# main.net
KiCad netlist of a schematic drawn in EAGLE
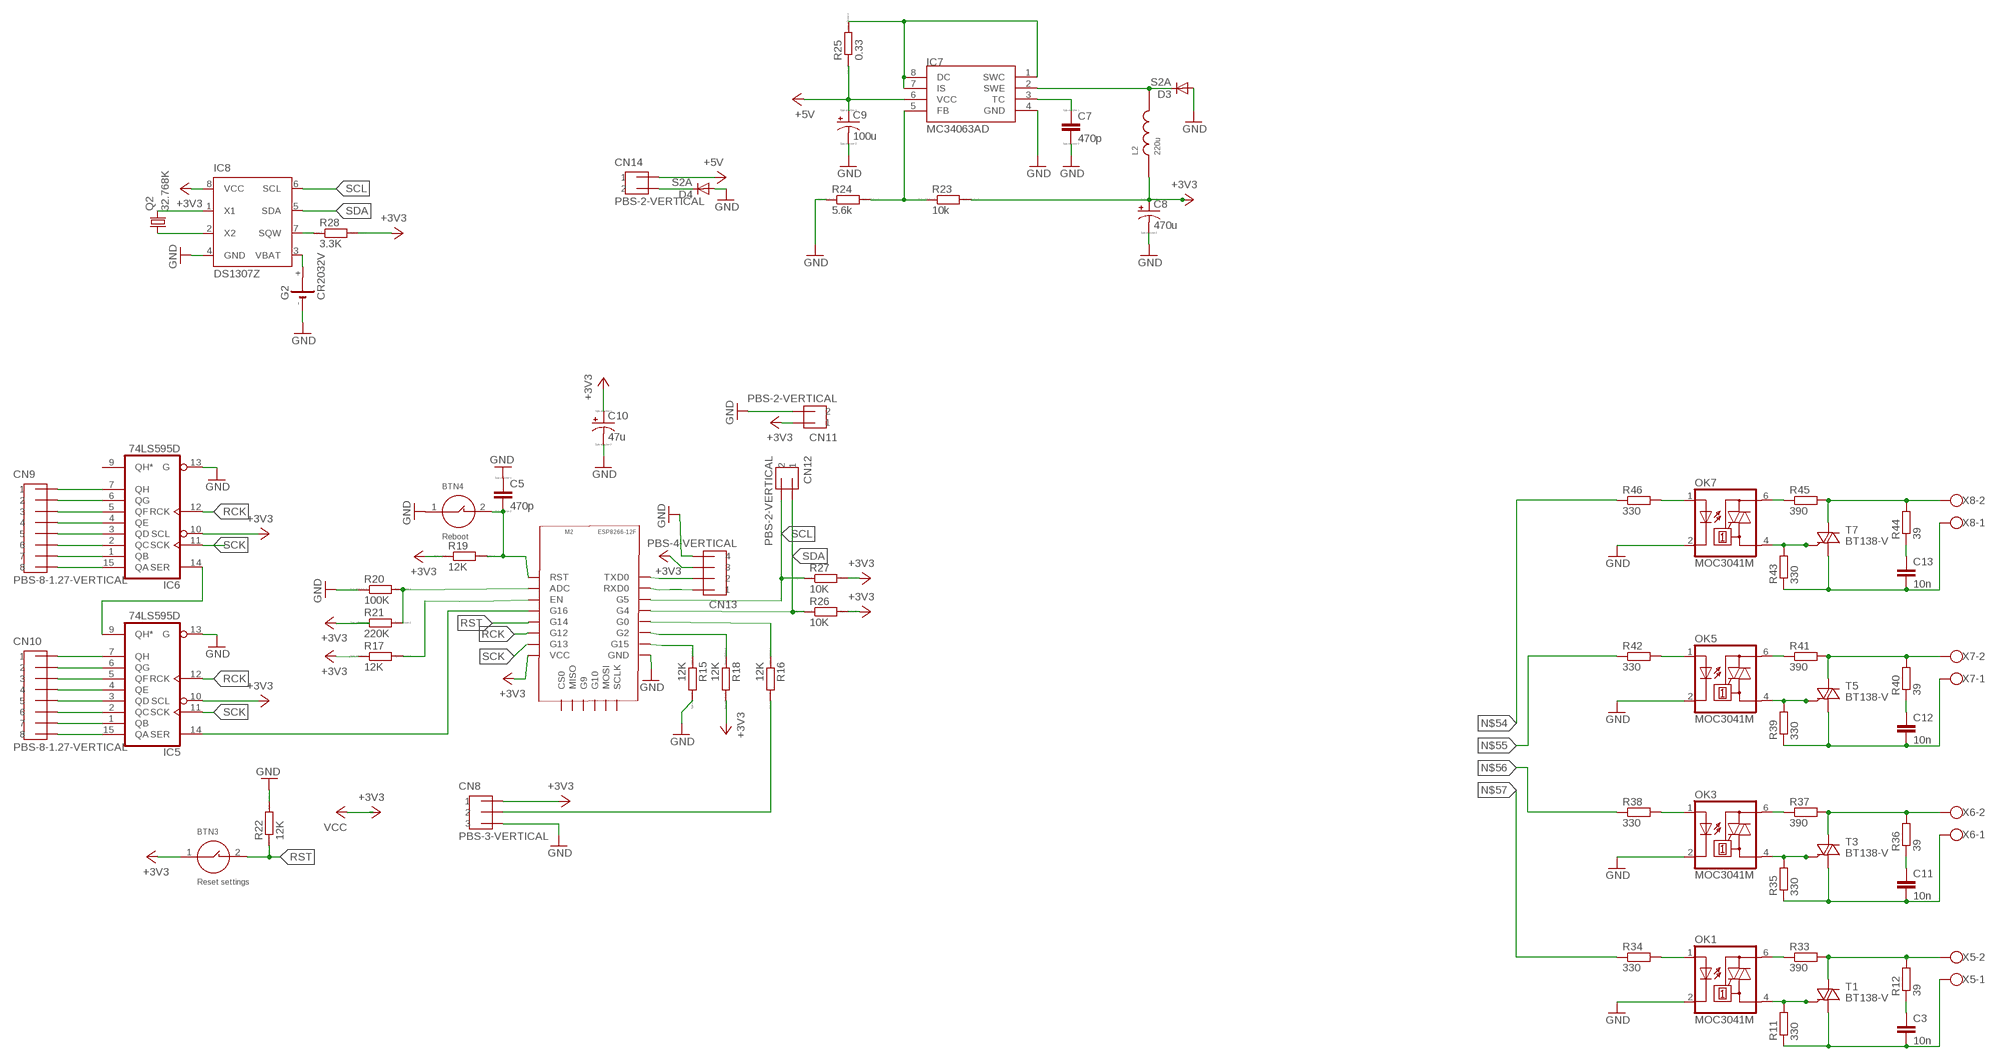
[diagram p0: schematic, sheet 1]

(export (version "E")
  (design (tool "Eeschema 10.0.6"))
  (components
    (comp (ref "BTN3")
      (value "Reset settings")
      (footprint "eagle-import:BTN-6X4-SMD")
      (libsource (lib "eagle-import") (part "BTN-6X4-SMD"))
    )
    (comp (ref "BTN4")
      (value "Reboot")
      (footprint "eagle-import:BTN-6X4-SMD")
      (libsource (lib "eagle-import") (part "BTN-6X4-SMD"))
    )
    (comp (ref "C3")
      (value "10n")
      (footprint "eagle-import:C10B5")
      (libsource (lib "eagle-import") (part "C10/5"))
    )
    (comp (ref "C5")
      (value "470p")
      (footprint "eagle-import:C0603")
      (libsource (lib "eagle-import") (part "CC0603"))
    )
    (comp (ref "C7")
      (value "470p")
      (footprint "eagle-import:C0603")
      (libsource (lib "eagle-import") (part "CC0603"))
    )
    (comp (ref "C8")
      (value "470u")
      (footprint "eagle-import:D_7343-31W")
      (libsource (lib "eagle-import") (part "CPOL-USD/7343-31W"))
    )
    (comp (ref "C9")
      (value "100u")
      (footprint "eagle-import:D_7343-31W")
      (libsource (lib "eagle-import") (part "CPOL-USD/7343-31W"))
    )
    (comp (ref "C10")
      (value "47u")
      (footprint "eagle-import:CT3216")
      (libsource (lib "eagle-import") (part "CPOL-USCT3216"))
    )
    (comp (ref "C11")
      (value "10n")
      (footprint "eagle-import:C10B5")
      (libsource (lib "eagle-import") (part "C10/5"))
    )
    (comp (ref "C12")
      (value "10n")
      (footprint "eagle-import:C10B5")
      (libsource (lib "eagle-import") (part "C10/5"))
    )
    (comp (ref "C13")
      (value "10n")
      (footprint "eagle-import:C10B5")
      (libsource (lib "eagle-import") (part "C10/5"))
    )
    (comp (ref "CN8")
      (value "PBS-3-VERTICAL")
      (footprint "eagle-import:PBS-3-VERTICAL")
      (libsource (lib "eagle-import") (part "PBS-3-VERTICAL"))
    )
    (comp (ref "CN9")
      (value "PBS-8-1.27-VERTICAL")
      (footprint "eagle-import:PBS-8-1.27-VERTICAL")
      (libsource (lib "eagle-import") (part "PBS-8-1.27-VERTICAL"))
    )
    (comp (ref "CN10")
      (value "PBS-8-1.27-VERTICAL")
      (footprint "eagle-import:PBS-8-1.27-VERTICAL")
      (libsource (lib "eagle-import") (part "PBS-8-1.27-VERTICAL"))
    )
    (comp (ref "CN11")
      (value "PBS-2-VERTICAL")
      (footprint "eagle-import:PBS-2-VERTICAL")
      (libsource (lib "eagle-import") (part "PBS-2-VERTICAL"))
    )
    (comp (ref "CN12")
      (value "PBS-2-VERTICAL")
      (footprint "eagle-import:PBS-2-VERTICAL")
      (libsource (lib "eagle-import") (part "PBS-2-VERTICAL"))
    )
    (comp (ref "CN13")
      (value "PBS-4-VERTICAL")
      (footprint "eagle-import:PBS-4-VERTICAL")
      (libsource (lib "eagle-import") (part "PBS-4-VERTICAL"))
    )
    (comp (ref "CN14")
      (value "PBS-2-VERTICAL")
      (footprint "eagle-import:PBS-2-VERTICAL")
      (libsource (lib "eagle-import") (part "PBS-2-VERTICAL"))
    )
    (comp (ref "D3")
      (value "S2A")
      (footprint "eagle-import:DO214AA")
      (fields (field (name "MF") "Fairchild"))
      (libsource (lib "eagle-import") (part "S2A"))
    )
    (comp (ref "D4")
      (value "S2A")
      (footprint "eagle-import:DO214AA")
      (fields (field (name "MF") "Fairchild"))
      (libsource (lib "eagle-import") (part "S2A"))
    )
    (comp (ref "G2")
      (value "CR2032V")
      (footprint "eagle-import:CR2032V")
      (libsource (lib "eagle-import") (part "CR2032V"))
    )
    (comp (ref "IC5")
      (value "74LS595D")
      (footprint "eagle-import:SO16")
      (libsource (lib "eagle-import") (part "74595DLS"))
    )
    (comp (ref "IC6")
      (value "74LS595D")
      (footprint "eagle-import:SO16")
      (libsource (lib "eagle-import") (part "74595DLS"))
    )
    (comp (ref "IC7")
      (value "MC34063AD")
      (footprint "eagle-import:SOIC8")
      (libsource (lib "eagle-import") (part "MC34063AD"))
    )
    (comp (ref "IC8")
      (value "DS1307Z")
      (footprint "eagle-import:SOIC8")
      (libsource (lib "eagle-import") (part "DS1307Z"))
    )
    (comp (ref "L2")
      (value "220u")
      (footprint "eagle-import:INDUCTOR-5-10")
      (libsource (lib "eagle-import") (part "INDUCTOR-5-10"))
    )
    (comp (ref "M2")
      (value "ESP8266-12F")
      (footprint "eagle-import:ESP8266-12F")
      (libsource (lib "eagle-import") (part "ESP8266-12F"))
    )
    (comp (ref "OK1")
      (value "MOC3041M")
      (footprint "eagle-import:DIL06")
      (fields (field (name "MF") "FAIRCHILD SEMICONDUCTOR"))
      (libsource (lib "eagle-import") (part "MOC3041M"))
    )
    (comp (ref "OK3")
      (value "MOC3041M")
      (footprint "eagle-import:DIL06")
      (fields (field (name "MF") "FAIRCHILD SEMICONDUCTOR"))
      (libsource (lib "eagle-import") (part "MOC3041M"))
    )
    (comp (ref "OK5")
      (value "MOC3041M")
      (footprint "eagle-import:DIL06")
      (fields (field (name "MF") "FAIRCHILD SEMICONDUCTOR"))
      (libsource (lib "eagle-import") (part "MOC3041M"))
    )
    (comp (ref "OK7")
      (value "MOC3041M")
      (footprint "eagle-import:DIL06")
      (fields (field (name "MF") "FAIRCHILD SEMICONDUCTOR"))
      (libsource (lib "eagle-import") (part "MOC3041M"))
    )
    (comp (ref "Q2")
      (value "32.768K")
      (footprint "eagle-import:TC38H")
      (libsource (lib "eagle-import") (part "CRYSTALTC38H"))
    )
    (comp (ref "R11")
      (value "330")
      (footprint "eagle-import:0411_12")
      (libsource (lib "eagle-import") (part "R-EU_0411/12"))
    )
    (comp (ref "R12")
      (value "39")
      (footprint "eagle-import:0411_12")
      (libsource (lib "eagle-import") (part "R-EU_0411/12"))
    )
    (comp (ref "R15")
      (value "12K")
      (footprint "eagle-import:R0603")
      (libsource (lib "eagle-import") (part "RR0603"))
    )
    (comp (ref "R16")
      (value "12K")
      (footprint "eagle-import:R0603")
      (libsource (lib "eagle-import") (part "RR0603"))
    )
    (comp (ref "R17")
      (value "12K")
      (footprint "eagle-import:R0603")
      (libsource (lib "eagle-import") (part "RR0603"))
    )
    (comp (ref "R18")
      (value "12K")
      (footprint "eagle-import:R0603")
      (libsource (lib "eagle-import") (part "RR0603"))
    )
    (comp (ref "R19")
      (value "12K")
      (footprint "eagle-import:R0603")
      (libsource (lib "eagle-import") (part "RR0603"))
    )
    (comp (ref "R20")
      (value "100K")
      (footprint "eagle-import:R0603")
      (libsource (lib "eagle-import") (part "RR0603"))
    )
    (comp (ref "R21")
      (value "220K")
      (footprint "eagle-import:R0603")
      (libsource (lib "eagle-import") (part "RR0603"))
    )
    (comp (ref "R22")
      (value "12K")
      (footprint "eagle-import:R0603")
      (libsource (lib "eagle-import") (part "RR0603"))
    )
    (comp (ref "R23")
      (value "10k")
      (footprint "eagle-import:R0603")
      (libsource (lib "eagle-import") (part "RR0603"))
    )
    (comp (ref "R24")
      (value "5.6k")
      (footprint "eagle-import:R0603")
      (libsource (lib "eagle-import") (part "RR0603"))
    )
    (comp (ref "R25")
      (value "0.33")
      (footprint "eagle-import:R0603")
      (libsource (lib "eagle-import") (part "RR0603"))
    )
    (comp (ref "R26")
      (value "10K")
      (footprint "eagle-import:R0603")
      (libsource (lib "eagle-import") (part "RR0603"))
    )
    (comp (ref "R27")
      (value "10K")
      (footprint "eagle-import:R0603")
      (libsource (lib "eagle-import") (part "RR0603"))
    )
    (comp (ref "R28")
      (value "3.3K")
      (footprint "eagle-import:R0603")
      (libsource (lib "eagle-import") (part "RR0603"))
    )
    (comp (ref "R33")
      (value "390")
      (footprint "eagle-import:0411_12")
      (libsource (lib "eagle-import") (part "R-EU_0411/12"))
    )
    (comp (ref "R34")
      (value "330")
      (footprint "eagle-import:R0603")
      (libsource (lib "eagle-import") (part "R-EU_R0603"))
    )
    (comp (ref "R35")
      (value "330")
      (footprint "eagle-import:0411_12")
      (libsource (lib "eagle-import") (part "R-EU_0411/12"))
    )
    (comp (ref "R36")
      (value "39")
      (footprint "eagle-import:0411_12")
      (libsource (lib "eagle-import") (part "R-EU_0411/12"))
    )
    (comp (ref "R37")
      (value "390")
      (footprint "eagle-import:0411_12")
      (libsource (lib "eagle-import") (part "R-EU_0411/12"))
    )
    (comp (ref "R38")
      (value "330")
      (footprint "eagle-import:R0603")
      (libsource (lib "eagle-import") (part "R-EU_R0603"))
    )
    (comp (ref "R39")
      (value "330")
      (footprint "eagle-import:0411_12")
      (libsource (lib "eagle-import") (part "R-EU_0411/12"))
    )
    (comp (ref "R40")
      (value "39")
      (footprint "eagle-import:0411_12")
      (libsource (lib "eagle-import") (part "R-EU_0411/12"))
    )
    (comp (ref "R41")
      (value "390")
      (footprint "eagle-import:0411_12")
      (libsource (lib "eagle-import") (part "R-EU_0411/12"))
    )
    (comp (ref "R42")
      (value "330")
      (footprint "eagle-import:R0603")
      (libsource (lib "eagle-import") (part "R-EU_R0603"))
    )
    (comp (ref "R43")
      (value "330")
      (footprint "eagle-import:0411_12")
      (libsource (lib "eagle-import") (part "R-EU_0411/12"))
    )
    (comp (ref "R44")
      (value "39")
      (footprint "eagle-import:0411_12")
      (libsource (lib "eagle-import") (part "R-EU_0411/12"))
    )
    (comp (ref "R45")
      (value "390")
      (footprint "eagle-import:0411_12")
      (libsource (lib "eagle-import") (part "R-EU_0411/12"))
    )
    (comp (ref "R46")
      (value "330")
      (footprint "eagle-import:R0603")
      (libsource (lib "eagle-import") (part "R-EU_R0603"))
    )
    (comp (ref "T1")
      (value "BT138-V")
      (footprint "eagle-import:TO220BV")
      (libsource (lib "eagle-import") (part "BT138-V"))
    )
    (comp (ref "T3")
      (value "BT138-V")
      (footprint "eagle-import:TO220BV")
      (libsource (lib "eagle-import") (part "BT138-V"))
    )
    (comp (ref "T5")
      (value "BT138-V")
      (footprint "eagle-import:TO220BV")
      (libsource (lib "eagle-import") (part "BT138-V"))
    )
    (comp (ref "T7")
      (value "BT138-V")
      (footprint "eagle-import:TO220BV")
      (libsource (lib "eagle-import") (part "BT138-V"))
    )
    (comp (ref "X5")
      (value "W237-102")
      (footprint "eagle-import:W237-102")
      (fields (field (name "MPN") "237-102"))
      (libsource (lib "eagle-import") (part "W237-102"))
    )
    (comp (ref "X6")
      (value "W237-102")
      (footprint "eagle-import:W237-102")
      (fields (field (name "MPN") "237-102"))
      (libsource (lib "eagle-import") (part "W237-102"))
    )
    (comp (ref "X7")
      (value "W237-102")
      (footprint "eagle-import:W237-102")
      (fields (field (name "MPN") "237-102"))
      (libsource (lib "eagle-import") (part "W237-102"))
    )
    (comp (ref "X8")
      (value "W237-102")
      (footprint "eagle-import:W237-102")
      (fields (field (name "MPN") "237-102"))
      (libsource (lib "eagle-import") (part "W237-102"))
    )
  )
  (nets
    (net (code "1") (name "+3V3") (class "Default")
      (node (ref "BTN3") (pin "1") (pinfunction "1_1") (pintype "bidirectional"))
      (node (ref "C10") (pin "-") (pinfunction "+_-") (pintype "passive"))
      (node (ref "C8") (pin "+") (pinfunction "+_+") (pintype "passive"))
      (node (ref "CN11") (pin "P$1") (pinfunction "1_P$1") (pintype "bidirectional"))
      (node (ref "CN13") (pin "P$3") (pinfunction "3_P$3") (pintype "bidirectional"))
      (node (ref "CN8") (pin "P$1") (pinfunction "1_P$1") (pintype "bidirectional"))
      (node (ref "IC5") (pin "10") (pinfunction "SCL_10") (pintype "input"))
      (node (ref "IC6") (pin "10") (pinfunction "SCL_10") (pintype "input"))
      (node (ref "IC8") (pin "8") (pinfunction "VCC_8") (pintype "power_in"))
      (node (ref "L2") (pin "P$1") (pinfunction "1_P$1") (pintype "bidirectional"))
      (node (ref "M2") (pin "VCC") (pinfunction "VCC_VCC") (pintype "power_in"))
      (node (ref "R17") (pin "1") (pinfunction "1_1") (pintype "passive"))
      (node (ref "R18") (pin "2") (pinfunction "2_2") (pintype "passive"))
      (node (ref "R19") (pin "1") (pinfunction "1_1") (pintype "passive"))
      (node (ref "R21") (pin "1") (pinfunction "1_1") (pintype "passive"))
      (node (ref "R23") (pin "2") (pinfunction "2_2") (pintype "passive"))
      (node (ref "R26") (pin "2") (pinfunction "2_2") (pintype "passive"))
      (node (ref "R27") (pin "2") (pinfunction "2_2") (pintype "passive"))
      (node (ref "R28") (pin "2") (pinfunction "2_2") (pintype "passive"))
    )
    (net (code "2") (name "+5V") (class "Default")
      (node (ref "C9") (pin "+") (pinfunction "+_+") (pintype "passive"))
      (node (ref "CN14") (pin "P$1") (pinfunction "1_P$1") (pintype "bidirectional"))
      (node (ref "IC7") (pin "6") (pinfunction "VCC_6") (pintype "passive"))
      (node (ref "R25") (pin "1") (pinfunction "1_1") (pintype "passive"))
    )
    (net (code "3") (name "/N$60") (class "Default")
      (node (ref "BTN4") (pin "2") (pinfunction "2_2") (pintype "bidirectional"))
      (node (ref "C5") (pin "2") (pinfunction "2_2") (pintype "passive"))
      (node (ref "M2") (pin "RST") (pinfunction "RST_RST") (pintype "bidirectional"))
      (node (ref "R19") (pin "2") (pinfunction "2_2") (pintype "passive"))
    )
    (net (code "4") (name "GND") (class "Default")
      (node (ref "BTN4") (pin "1") (pinfunction "1_1") (pintype "bidirectional"))
      (node (ref "C10") (pin "+") (pinfunction "-_+") (pintype "passive"))
      (node (ref "C5") (pin "1") (pinfunction "1_1") (pintype "passive"))
      (node (ref "C7") (pin "2") (pinfunction "2_2") (pintype "passive"))
      (node (ref "C8") (pin "-") (pinfunction "-_-") (pintype "passive"))
      (node (ref "C9") (pin "-") (pinfunction "-_-") (pintype "passive"))
      (node (ref "CN11") (pin "P$2") (pinfunction "2_P$2") (pintype "bidirectional"))
      (node (ref "CN13") (pin "P$4") (pinfunction "4_P$4") (pintype "bidirectional"))
      (node (ref "CN8") (pin "P$3") (pinfunction "3_P$3") (pintype "bidirectional"))
      (node (ref "D3") (pin "A") (pinfunction "A_A") (pintype "passive"))
      (node (ref "D4") (pin "A") (pinfunction "A_A") (pintype "passive"))
      (node (ref "G2") (pin "-") (pinfunction "-_-") (pintype "passive"))
      (node (ref "IC5") (pin "13") (pinfunction "G_13") (pintype "input"))
      (node (ref "IC6") (pin "13") (pinfunction "G_13") (pintype "input"))
      (node (ref "IC7") (pin "4") (pinfunction "GND_4") (pintype "passive"))
      (node (ref "IC8") (pin "4") (pinfunction "GND_4") (pintype "power_in"))
      (node (ref "M2") (pin "GND") (pinfunction "GND_GND") (pintype "power_in"))
      (node (ref "OK1") (pin "2") (pinfunction "C_2") (pintype "passive"))
      (node (ref "OK3") (pin "2") (pinfunction "C_2") (pintype "passive"))
      (node (ref "OK5") (pin "2") (pinfunction "C_2") (pintype "passive"))
      (node (ref "OK7") (pin "2") (pinfunction "C_2") (pintype "passive"))
      (node (ref "R15") (pin "2") (pinfunction "2_2") (pintype "passive"))
      (node (ref "R20") (pin "1") (pinfunction "1_1") (pintype "passive"))
      (node (ref "R22") (pin "2") (pinfunction "2_2") (pintype "passive"))
      (node (ref "R24") (pin "1") (pinfunction "1_1") (pintype "passive"))
    )
    (net (code "5") (name "N$54") (class "Default")
      (node (ref "CN10") (pin "P$5") (pinfunction "5_P$5") (pintype "bidirectional"))
      (node (ref "IC5") (pin "3") (pinfunction "QD_3") (pintype "tri_state"))
      (node (ref "R46") (pin "1") (pinfunction "1_1") (pintype "passive"))
    )
    (net (code "6") (name "N$55") (class "Default")
      (node (ref "CN10") (pin "P$6") (pinfunction "6_P$6") (pintype "bidirectional"))
      (node (ref "IC5") (pin "2") (pinfunction "QC_2") (pintype "tri_state"))
      (node (ref "R42") (pin "1") (pinfunction "1_1") (pintype "passive"))
    )
    (net (code "7") (name "N$56") (class "Default")
      (node (ref "CN10") (pin "P$7") (pinfunction "7_P$7") (pintype "bidirectional"))
      (node (ref "IC5") (pin "1") (pinfunction "QB_1") (pintype "tri_state"))
      (node (ref "R38") (pin "1") (pinfunction "1_1") (pintype "passive"))
    )
    (net (code "8") (name "N$57") (class "Default")
      (node (ref "CN10") (pin "P$8") (pinfunction "8_P$8") (pintype "bidirectional"))
      (node (ref "IC5") (pin "15") (pinfunction "QA_15") (pintype "tri_state"))
      (node (ref "R34") (pin "1") (pinfunction "1_1") (pintype "passive"))
    )
    (net (code "9") (name "Net-(C3-Pad1)") (class "Default")
      (node (ref "C3") (pin "1") (pinfunction "1_1") (pintype "passive"))
      (node (ref "R12") (pin "1") (pinfunction "1_1") (pintype "passive"))
    )
    (net (code "10") (name "Net-(C11-Pad1)") (class "Default")
      (node (ref "C11") (pin "1") (pinfunction "1_1") (pintype "passive"))
      (node (ref "R36") (pin "1") (pinfunction "1_1") (pintype "passive"))
    )
    (net (code "11") (name "Net-(C12-Pad1)") (class "Default")
      (node (ref "C12") (pin "1") (pinfunction "1_1") (pintype "passive"))
      (node (ref "R40") (pin "1") (pinfunction "1_1") (pintype "passive"))
    )
    (net (code "12") (name "Net-(C13-Pad1)") (class "Default")
      (node (ref "C13") (pin "1") (pinfunction "1_1") (pintype "passive"))
      (node (ref "R44") (pin "1") (pinfunction "1_1") (pintype "passive"))
    )
    (net (code "13") (name "Net-(CN8-2)") (class "Default")
      (node (ref "CN8") (pin "P$2") (pinfunction "2_P$2") (pintype "bidirectional"))
      (node (ref "R16") (pin "2") (pinfunction "2_2") (pintype "passive"))
    )
    (net (code "14") (name "Net-(CN9-1)") (class "Default")
      (node (ref "CN9") (pin "P$1") (pinfunction "1_P$1") (pintype "bidirectional"))
      (node (ref "IC6") (pin "7") (pinfunction "QH_7") (pintype "tri_state"))
    )
    (net (code "15") (name "Net-(CN9-2)") (class "Default")
      (node (ref "CN9") (pin "P$2") (pinfunction "2_P$2") (pintype "bidirectional"))
      (node (ref "IC6") (pin "6") (pinfunction "QG_6") (pintype "tri_state"))
    )
    (net (code "16") (name "Net-(CN9-3)") (class "Default")
      (node (ref "CN9") (pin "P$3") (pinfunction "3_P$3") (pintype "bidirectional"))
      (node (ref "IC6") (pin "5") (pinfunction "QF_5") (pintype "tri_state"))
    )
    (net (code "17") (name "Net-(CN9-4)") (class "Default")
      (node (ref "CN9") (pin "P$4") (pinfunction "4_P$4") (pintype "bidirectional"))
      (node (ref "IC6") (pin "4") (pinfunction "QE_4") (pintype "tri_state"))
    )
    (net (code "18") (name "Net-(CN9-5)") (class "Default")
      (node (ref "CN9") (pin "P$5") (pinfunction "5_P$5") (pintype "bidirectional"))
      (node (ref "IC6") (pin "3") (pinfunction "QD_3") (pintype "tri_state"))
    )
    (net (code "19") (name "Net-(CN9-6)") (class "Default")
      (node (ref "CN9") (pin "P$6") (pinfunction "6_P$6") (pintype "bidirectional"))
      (node (ref "IC6") (pin "2") (pinfunction "QC_2") (pintype "tri_state"))
    )
    (net (code "20") (name "Net-(CN9-7)") (class "Default")
      (node (ref "CN9") (pin "P$7") (pinfunction "7_P$7") (pintype "bidirectional"))
      (node (ref "IC6") (pin "1") (pinfunction "QB_1") (pintype "tri_state"))
    )
    (net (code "21") (name "Net-(CN9-8)") (class "Default")
      (node (ref "CN9") (pin "P$8") (pinfunction "8_P$8") (pintype "bidirectional"))
      (node (ref "IC6") (pin "15") (pinfunction "QA_15") (pintype "tri_state"))
    )
    (net (code "22") (name "Net-(CN10-1)") (class "Default")
      (node (ref "CN10") (pin "P$1") (pinfunction "1_P$1") (pintype "bidirectional"))
      (node (ref "IC5") (pin "7") (pinfunction "QH_7") (pintype "tri_state"))
    )
    (net (code "23") (name "Net-(CN10-2)") (class "Default")
      (node (ref "CN10") (pin "P$2") (pinfunction "2_P$2") (pintype "bidirectional"))
      (node (ref "IC5") (pin "6") (pinfunction "QG_6") (pintype "tri_state"))
    )
    (net (code "24") (name "Net-(CN10-3)") (class "Default")
      (node (ref "CN10") (pin "P$3") (pinfunction "3_P$3") (pintype "bidirectional"))
      (node (ref "IC5") (pin "5") (pinfunction "QF_5") (pintype "tri_state"))
    )
    (net (code "25") (name "Net-(CN10-4)") (class "Default")
      (node (ref "CN10") (pin "P$4") (pinfunction "4_P$4") (pintype "bidirectional"))
      (node (ref "IC5") (pin "4") (pinfunction "QE_4") (pintype "tri_state"))
    )
    (net (code "26") (name "Net-(CN13-1)") (class "Default")
      (node (ref "CN13") (pin "P$1") (pinfunction "1_P$1") (pintype "bidirectional"))
      (node (ref "M2") (pin "RXD0") (pinfunction "RXD0_RXD0") (pintype "bidirectional"))
    )
    (net (code "27") (name "Net-(CN13-2)") (class "Default")
      (node (ref "CN13") (pin "P$2") (pinfunction "2_P$2") (pintype "bidirectional"))
      (node (ref "M2") (pin "TXD0") (pinfunction "TXD0_TXD0") (pintype "bidirectional"))
    )
    (net (code "28") (name "Net-(CN14-2)") (class "Default")
      (node (ref "CN14") (pin "P$2") (pinfunction "2_P$2") (pintype "bidirectional"))
      (node (ref "D4") (pin "C") (pinfunction "C_C") (pintype "passive"))
    )
    (net (code "29") (name "Net-(IC5A-QH*)") (class "Default")
      (node (ref "IC5") (pin "9") (pinfunction "QH*_9") (pintype "tri_state"))
      (node (ref "IC6") (pin "14") (pinfunction "SER_14") (pintype "input"))
    )
    (net (code "30") (name "Net-(IC5A-SER)") (class "Default")
      (node (ref "IC5") (pin "14") (pinfunction "SER_14") (pintype "input"))
      (node (ref "M2") (pin "G16") (pinfunction "G16_G16") (pintype "bidirectional"))
    )
    (net (code "31") (name "Net-(IC7-DC)") (class "Default")
      (node (ref "IC7") (pin "1") (pinfunction "SWC_1") (pintype "passive"))
      (node (ref "IC7") (pin "7") (pinfunction "IS_7") (pintype "passive"))
      (node (ref "IC7") (pin "8") (pinfunction "DC_8") (pintype "passive"))
      (node (ref "R25") (pin "2") (pinfunction "2_2") (pintype "passive"))
    )
    (net (code "32") (name "Net-(IC7-FB)") (class "Default")
      (node (ref "IC7") (pin "5") (pinfunction "FB_5") (pintype "passive"))
      (node (ref "R23") (pin "1") (pinfunction "1_1") (pintype "passive"))
      (node (ref "R24") (pin "2") (pinfunction "2_2") (pintype "passive"))
    )
    (net (code "33") (name "Net-(IC7-SWE)") (class "Default")
      (node (ref "D3") (pin "C") (pinfunction "C_C") (pintype "passive"))
      (node (ref "IC7") (pin "2") (pinfunction "SWE_2") (pintype "passive"))
      (node (ref "L2") (pin "P$2") (pinfunction "P$2_P$2") (pintype "bidirectional"))
    )
    (net (code "34") (name "Net-(IC7-TC)") (class "Default")
      (node (ref "C7") (pin "1") (pinfunction "1_1") (pintype "passive"))
      (node (ref "IC7") (pin "3") (pinfunction "TC_3") (pintype "passive"))
    )
    (net (code "35") (name "Net-(IC8-SQW)") (class "Default")
      (node (ref "IC8") (pin "7") (pinfunction "SQW_7") (pintype "open_collector"))
      (node (ref "R28") (pin "1") (pinfunction "1_1") (pintype "passive"))
    )
    (net (code "36") (name "Net-(IC8-VBAT)") (class "Default")
      (node (ref "G2") (pin "+") (pinfunction "+_+") (pintype "passive"))
      (node (ref "IC8") (pin "3") (pinfunction "VBAT_3") (pintype "passive"))
    )
    (net (code "37") (name "Net-(IC8-X1)") (class "Default")
      (node (ref "IC8") (pin "1") (pinfunction "X1_1") (pintype "input"))
      (node (ref "Q2") (pin "2") (pinfunction "2_2") (pintype "passive"))
    )
    (net (code "38") (name "Net-(IC8-X2)") (class "Default")
      (node (ref "IC8") (pin "2") (pinfunction "X2_2") (pintype "output"))
      (node (ref "Q2") (pin "1") (pinfunction "1_1") (pintype "passive"))
    )
    (net (code "39") (name "Net-(M2-PadADC)") (class "Default")
      (node (ref "M2") (pin "ADC") (pinfunction "ADC_ADC") (pintype "bidirectional"))
      (node (ref "R20") (pin "2") (pinfunction "2_2") (pintype "passive"))
      (node (ref "R21") (pin "2") (pinfunction "2_2") (pintype "passive"))
    )
    (net (code "40") (name "Net-(M2-PadEN)") (class "Default")
      (node (ref "M2") (pin "EN") (pinfunction "EN_EN") (pintype "bidirectional"))
      (node (ref "R17") (pin "2") (pinfunction "2_2") (pintype "passive"))
    )
    (net (code "41") (name "Net-(M2-PadG0)") (class "Default")
      (node (ref "M2") (pin "G0") (pinfunction "G0_G0") (pintype "bidirectional"))
      (node (ref "R16") (pin "1") (pinfunction "1_1") (pintype "passive"))
    )
    (net (code "42") (name "Net-(M2-PadG2)") (class "Default")
      (node (ref "M2") (pin "G2") (pinfunction "G2_G2") (pintype "bidirectional"))
      (node (ref "R18") (pin "1") (pinfunction "1_1") (pintype "passive"))
    )
    (net (code "43") (name "Net-(M2-PadG15)") (class "Default")
      (node (ref "M2") (pin "G15") (pinfunction "G15_G15") (pintype "bidirectional"))
      (node (ref "R15") (pin "1") (pinfunction "1_1") (pintype "passive"))
    )
    (net (code "44") (name "Net-(OK1-A)") (class "Default")
      (node (ref "OK1") (pin "1") (pinfunction "A_1") (pintype "passive"))
      (node (ref "R34") (pin "2") (pinfunction "2_2") (pintype "passive"))
    )
    (net (code "45") (name "Net-(OK1-A1)") (class "Default")
      (node (ref "OK1") (pin "4") (pinfunction "A1_4") (pintype "passive"))
      (node (ref "R11") (pin "2") (pinfunction "2_2") (pintype "passive"))
      (node (ref "T1") (pin "G") (pinfunction "G_G") (pintype "passive"))
    )
    (net (code "46") (name "Net-(OK1-A2)") (class "Default")
      (node (ref "OK1") (pin "6") (pinfunction "A2_6") (pintype "passive"))
      (node (ref "R33") (pin "1") (pinfunction "1_1") (pintype "passive"))
    )
    (net (code "47") (name "Net-(OK3-A)") (class "Default")
      (node (ref "OK3") (pin "1") (pinfunction "A_1") (pintype "passive"))
      (node (ref "R38") (pin "2") (pinfunction "2_2") (pintype "passive"))
    )
    (net (code "48") (name "Net-(OK3-A1)") (class "Default")
      (node (ref "OK3") (pin "4") (pinfunction "A1_4") (pintype "passive"))
      (node (ref "R35") (pin "2") (pinfunction "2_2") (pintype "passive"))
      (node (ref "T3") (pin "G") (pinfunction "G_G") (pintype "passive"))
    )
    (net (code "49") (name "Net-(OK3-A2)") (class "Default")
      (node (ref "OK3") (pin "6") (pinfunction "A2_6") (pintype "passive"))
      (node (ref "R37") (pin "1") (pinfunction "1_1") (pintype "passive"))
    )
    (net (code "50") (name "Net-(OK5-A)") (class "Default")
      (node (ref "OK5") (pin "1") (pinfunction "A_1") (pintype "passive"))
      (node (ref "R42") (pin "2") (pinfunction "2_2") (pintype "passive"))
    )
    (net (code "51") (name "Net-(OK5-A1)") (class "Default")
      (node (ref "OK5") (pin "4") (pinfunction "A1_4") (pintype "passive"))
      (node (ref "R39") (pin "2") (pinfunction "2_2") (pintype "passive"))
      (node (ref "T5") (pin "G") (pinfunction "G_G") (pintype "passive"))
    )
    (net (code "52") (name "Net-(OK5-A2)") (class "Default")
      (node (ref "OK5") (pin "6") (pinfunction "A2_6") (pintype "passive"))
      (node (ref "R41") (pin "1") (pinfunction "1_1") (pintype "passive"))
    )
    (net (code "53") (name "Net-(OK7-A)") (class "Default")
      (node (ref "OK7") (pin "1") (pinfunction "A_1") (pintype "passive"))
      (node (ref "R46") (pin "2") (pinfunction "2_2") (pintype "passive"))
    )
    (net (code "54") (name "Net-(OK7-A1)") (class "Default")
      (node (ref "OK7") (pin "4") (pinfunction "A1_4") (pintype "passive"))
      (node (ref "R43") (pin "2") (pinfunction "2_2") (pintype "passive"))
      (node (ref "T7") (pin "G") (pinfunction "G_G") (pintype "passive"))
    )
    (net (code "55") (name "Net-(OK7-A2)") (class "Default")
      (node (ref "OK7") (pin "6") (pinfunction "A2_6") (pintype "passive"))
      (node (ref "R45") (pin "1") (pinfunction "1_1") (pintype "passive"))
    )
    (net (code "56") (name "Net-(T1-A1)") (class "Default")
      (node (ref "C3") (pin "2") (pinfunction "2_2") (pintype "passive"))
      (node (ref "R11") (pin "1") (pinfunction "1_1") (pintype "passive"))
      (node (ref "T1") (pin "T1") (pinfunction "A1_T1") (pintype "passive"))
      (node (ref "X5") (pin "1") (pinfunction "KL_1") (pintype "passive"))
    )
    (net (code "57") (name "Net-(T1-A2)") (class "Default")
      (node (ref "R12") (pin "2") (pinfunction "2_2") (pintype "passive"))
      (node (ref "R33") (pin "2") (pinfunction "2_2") (pintype "passive"))
      (node (ref "T1") (pin "T2") (pinfunction "A2_T2") (pintype "passive"))
      (node (ref "X5") (pin "2") (pinfunction "KL_2") (pintype "passive"))
    )
    (net (code "58") (name "Net-(T3-A1)") (class "Default")
      (node (ref "C11") (pin "2") (pinfunction "2_2") (pintype "passive"))
      (node (ref "R35") (pin "1") (pinfunction "1_1") (pintype "passive"))
      (node (ref "T3") (pin "T1") (pinfunction "A1_T1") (pintype "passive"))
      (node (ref "X6") (pin "1") (pinfunction "KL_1") (pintype "passive"))
    )
    (net (code "59") (name "Net-(T3-A2)") (class "Default")
      (node (ref "R36") (pin "2") (pinfunction "2_2") (pintype "passive"))
      (node (ref "R37") (pin "2") (pinfunction "2_2") (pintype "passive"))
      (node (ref "T3") (pin "T2") (pinfunction "A2_T2") (pintype "passive"))
      (node (ref "X6") (pin "2") (pinfunction "KL_2") (pintype "passive"))
    )
    (net (code "60") (name "Net-(T5-A1)") (class "Default")
      (node (ref "C12") (pin "2") (pinfunction "2_2") (pintype "passive"))
      (node (ref "R39") (pin "1") (pinfunction "1_1") (pintype "passive"))
      (node (ref "T5") (pin "T1") (pinfunction "A1_T1") (pintype "passive"))
      (node (ref "X7") (pin "1") (pinfunction "KL_1") (pintype "passive"))
    )
    (net (code "61") (name "Net-(T5-A2)") (class "Default")
      (node (ref "R40") (pin "2") (pinfunction "2_2") (pintype "passive"))
      (node (ref "R41") (pin "2") (pinfunction "2_2") (pintype "passive"))
      (node (ref "T5") (pin "T2") (pinfunction "A2_T2") (pintype "passive"))
      (node (ref "X7") (pin "2") (pinfunction "KL_2") (pintype "passive"))
    )
    (net (code "62") (name "Net-(T7-A1)") (class "Default")
      (node (ref "C13") (pin "2") (pinfunction "2_2") (pintype "passive"))
      (node (ref "R43") (pin "1") (pinfunction "1_1") (pintype "passive"))
      (node (ref "T7") (pin "T1") (pinfunction "A1_T1") (pintype "passive"))
      (node (ref "X8") (pin "1") (pinfunction "KL_1") (pintype "passive"))
    )
    (net (code "63") (name "Net-(T7-A2)") (class "Default")
      (node (ref "R44") (pin "2") (pinfunction "2_2") (pintype "passive"))
      (node (ref "R45") (pin "2") (pinfunction "2_2") (pintype "passive"))
      (node (ref "T7") (pin "T2") (pinfunction "A2_T2") (pintype "passive"))
      (node (ref "X8") (pin "2") (pinfunction "KL_2") (pintype "passive"))
    )
    (net (code "64") (name "RCK") (class "Default")
      (node (ref "IC5") (pin "12") (pinfunction "RCK_12") (pintype "input"))
      (node (ref "IC6") (pin "12") (pinfunction "RCK_12") (pintype "input"))
      (node (ref "M2") (pin "G12") (pinfunction "G12_G12") (pintype "bidirectional"))
    )
    (net (code "65") (name "RST") (class "Default")
      (node (ref "BTN3") (pin "2") (pinfunction "2_2") (pintype "bidirectional"))
      (node (ref "M2") (pin "G14") (pinfunction "G14_G14") (pintype "bidirectional"))
      (node (ref "R22") (pin "1") (pinfunction "1_1") (pintype "passive"))
    )
    (net (code "66") (name "SCK") (class "Default")
      (node (ref "IC5") (pin "11") (pinfunction "SCK_11") (pintype "input"))
      (node (ref "IC6") (pin "11") (pinfunction "SCK_11") (pintype "input"))
      (node (ref "M2") (pin "G13") (pinfunction "G13_G13") (pintype "bidirectional"))
    )
    (net (code "67") (name "SCL") (class "Default")
      (node (ref "CN12") (pin "P$2") (pinfunction "2_P$2") (pintype "bidirectional"))
      (node (ref "IC8") (pin "6") (pinfunction "SCL_6") (pintype "input"))
      (node (ref "M2") (pin "G5") (pinfunction "G5_G5") (pintype "bidirectional"))
      (node (ref "R27") (pin "1") (pinfunction "1_1") (pintype "passive"))
    )
    (net (code "68") (name "SDA") (class "Default")
      (node (ref "CN12") (pin "P$1") (pinfunction "1_P$1") (pintype "bidirectional"))
      (node (ref "IC8") (pin "5") (pinfunction "SDA_5") (pintype "bidirectional"))
      (node (ref "M2") (pin "G4") (pinfunction "G4_G4") (pintype "bidirectional"))
      (node (ref "R26") (pin "1") (pinfunction "1_1") (pintype "passive"))
    )
    (net (code "69") (name "unconnected-(G2-+-Pad+@1)") (class "Default")
      (node (ref "G2") (pin "+@1") (pinfunction "+_+@1") (pintype "passive"))
    )
    (net (code "70") (name "unconnected-(IC6A-QH*-Pad9)") (class "Default")
      (node (ref "IC6") (pin "9") (pinfunction "QH*_9") (pintype "tri_state"))
    )
    (net (code "71") (name "unconnected-(M2-PadCS0)") (class "Default")
      (node (ref "M2") (pin "CS0") (pinfunction "CS0_CS0") (pintype "bidirectional"))
    )
    (net (code "72") (name "unconnected-(M2-PadG9)") (class "Default")
      (node (ref "M2") (pin "G9") (pinfunction "G9_G9") (pintype "bidirectional"))
    )
    (net (code "73") (name "unconnected-(M2-PadG10)") (class "Default")
      (node (ref "M2") (pin "G10") (pinfunction "G10_G10") (pintype "bidirectional"))
    )
    (net (code "74") (name "unconnected-(M2-PadMISO)") (class "Default")
      (node (ref "M2") (pin "MISO") (pinfunction "MISO_MISO") (pintype "bidirectional"))
    )
    (net (code "75") (name "unconnected-(M2-PadMOSI)") (class "Default")
      (node (ref "M2") (pin "MOSI") (pinfunction "MOSI_MOSI") (pintype "bidirectional"))
    )
    (net (code "76") (name "unconnected-(M2-PadSCLK)") (class "Default")
      (node (ref "M2") (pin "SCLK") (pinfunction "SCLK_SCLK") (pintype "bidirectional"))
    )
  )
)
